# 1.net
KiCad netlist of a schematic drawn in Altium Designer
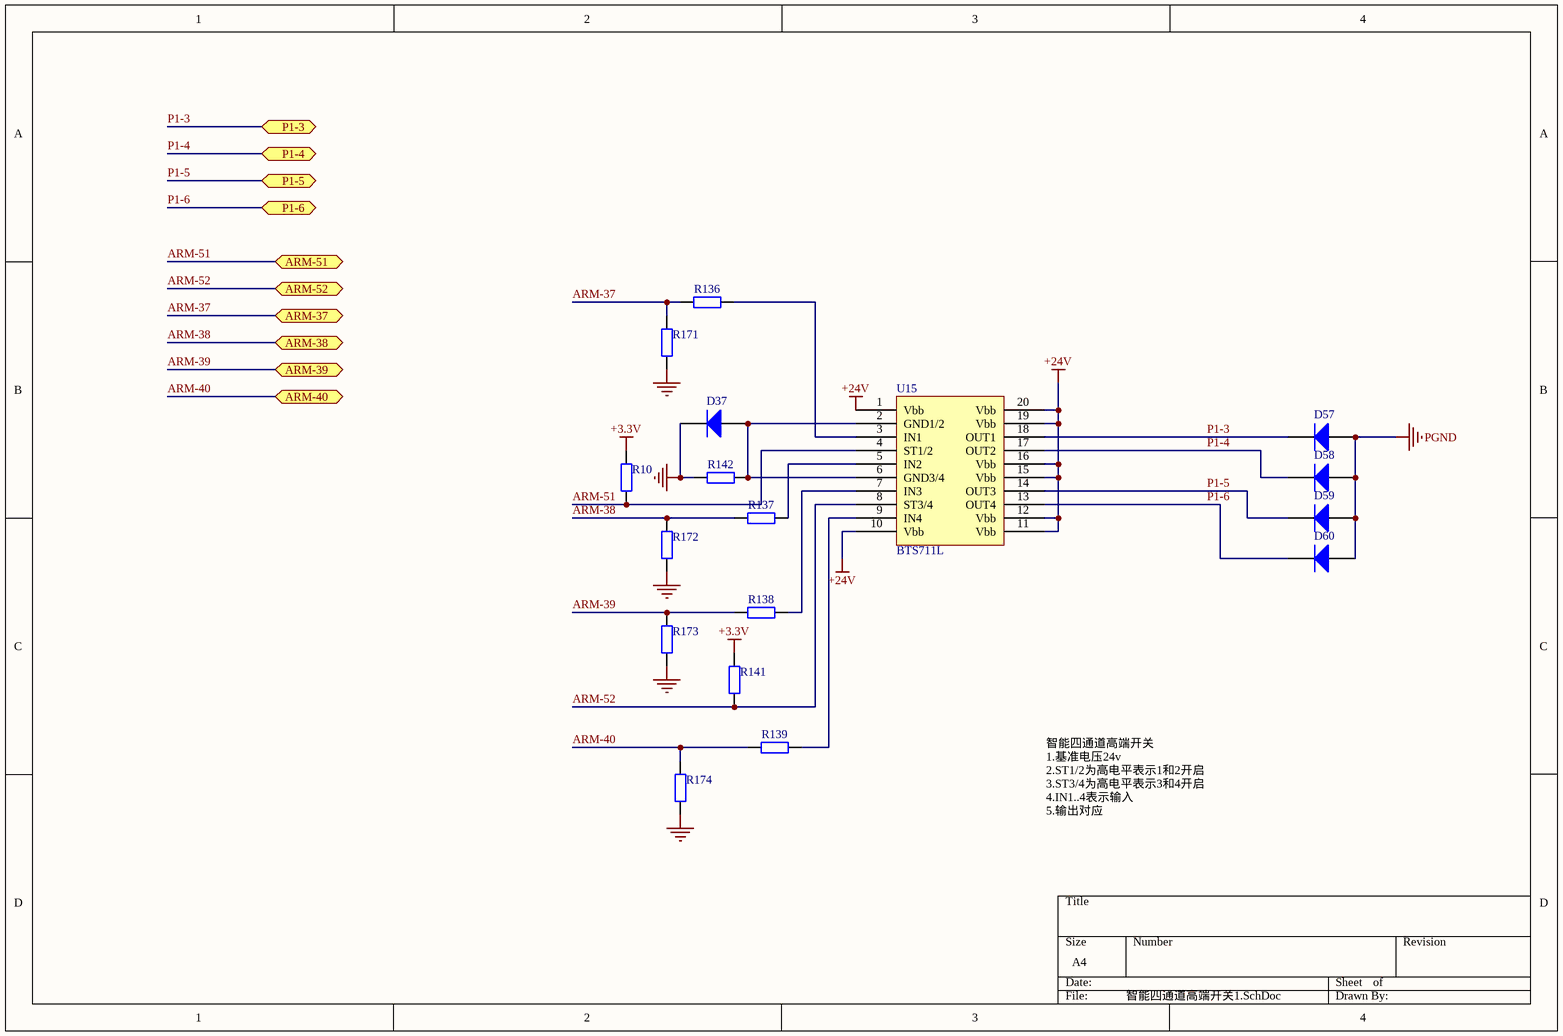
[diagram p0: 智能四通道高端开关1.SchDoc]

(export (version "E")
  (design (tool "Eeschema 10.0.6"))
  (components
    (comp (ref "D37")
      (value "Diode 1N4007")
      (footprint "DO-41")
      (description "1 Amp General Purpose Rectifier")
      (fields (field (name "PUBLISHER") "Altium Limited"))
      (libsource (lib "Miscellaneous Devices") (part "Diode 1N4007"))
    )
    (comp (ref "D57")
      (value "Diode 1N4007")
      (footprint "DO-41")
      (description "1 Amp General Purpose Rectifier")
      (fields (field (name "PUBLISHER") "Altium Limited"))
      (libsource (lib "Miscellaneous Devices") (part "Diode 1N4007"))
    )
    (comp (ref "D58")
      (value "Diode 1N4007")
      (footprint "DO-41")
      (description "1 Amp General Purpose Rectifier")
      (fields (field (name "PUBLISHER") "Altium Limited"))
      (libsource (lib "Miscellaneous Devices") (part "Diode 1N4007"))
    )
    (comp (ref "D59")
      (value "Diode 1N4007")
      (footprint "DO-41")
      (description "1 Amp General Purpose Rectifier")
      (fields (field (name "PUBLISHER") "Altium Limited"))
      (libsource (lib "Miscellaneous Devices") (part "Diode 1N4007"))
    )
    (comp (ref "D60")
      (value "Diode 1N4007")
      (footprint "DO-41")
      (description "1 Amp General Purpose Rectifier")
      (fields (field (name "PUBLISHER") "Altium Limited"))
      (libsource (lib "Miscellaneous Devices") (part "Diode 1N4007"))
    )
    (comp (ref "R10")
      (value "Res2")
      (footprint "AXIAL-0.4")
      (description "Resistor")
      (fields (field (name "PUBLISHER") "Altium Limited"))
      (libsource (lib "Miscellaneous Devices") (part "Res2"))
    )
    (comp (ref "R136")
      (value "Res2")
      (footprint "AXIAL-0.4")
      (description "Resistor")
      (fields (field (name "PUBLISHER") "Altium Limited"))
      (libsource (lib "") (part "Res2_1"))
    )
    (comp (ref "R137")
      (value "Res2")
      (footprint "AXIAL-0.4")
      (description "Resistor")
      (fields (field (name "PUBLISHER") "Altium Limited"))
      (libsource (lib "") (part "Res2_1"))
    )
    (comp (ref "R138")
      (value "Res2")
      (footprint "AXIAL-0.4")
      (description "Resistor")
      (fields (field (name "PUBLISHER") "Altium Limited"))
      (libsource (lib "") (part "Res2_1"))
    )
    (comp (ref "R139")
      (value "Res2")
      (footprint "AXIAL-0.4")
      (description "Resistor")
      (fields (field (name "PUBLISHER") "Altium Limited"))
      (libsource (lib "") (part "Res2_2"))
    )
    (comp (ref "R141")
      (value "Res2")
      (footprint "AXIAL-0.4")
      (description "Resistor")
      (fields (field (name "PUBLISHER") "Altium Limited"))
      (libsource (lib "Miscellaneous Devices") (part "Res2"))
    )
    (comp (ref "R142")
      (value "Res2")
      (footprint "AXIAL-0.4")
      (description "Resistor")
      (fields (field (name "PUBLISHER") "Altium Limited"))
      (libsource (lib "") (part "Res2_1"))
    )
    (comp (ref "R171")
      (value "Res2")
      (footprint "AXIAL-0.4")
      (description "Resistor")
      (fields (field (name "PUBLISHER") "Altium Limited"))
      (libsource (lib "Miscellaneous Devices") (part "Res2"))
    )
    (comp (ref "R172")
      (value "Res2")
      (footprint "AXIAL-0.4")
      (description "Resistor")
      (fields (field (name "PUBLISHER") "Altium Limited"))
      (libsource (lib "Miscellaneous Devices") (part "Res2"))
    )
    (comp (ref "R173")
      (value "Res2")
      (footprint "AXIAL-0.4")
      (description "Resistor")
      (fields (field (name "PUBLISHER") "Altium Limited"))
      (libsource (lib "Miscellaneous Devices") (part "Res2"))
    )
    (comp (ref "R174")
      (value "Res2")
      (footprint "AXIAL-0.4")
      (description "Resistor")
      (fields (field (name "PUBLISHER") "Altium Limited"))
      (libsource (lib "Miscellaneous Devices") (part "Res2"))
    )
    (comp (ref "U15") (value "BTS711L") (libsource (lib "BTS711L1") (part "Component_1")))
  )
  (nets
    (net (code "1") (name "+3.3V") (class "Default")
      (node (ref "R10") (pin "2") (pinfunction "2_2") (pintype "passive"))
      (node (ref "R141") (pin "2") (pinfunction "2_2") (pintype "passive"))
    )
    (net (code "2") (name "+24V") (class "Default")
      (node (ref "U15") (pin "1") (pinfunction "Vbb_1") (pintype "passive"))
      (node (ref "U15") (pin "10") (pinfunction "Vbb_10") (pintype "passive"))
      (node (ref "U15") (pin "11") (pinfunction "Vbb_11") (pintype "passive"))
      (node (ref "U15") (pin "12") (pinfunction "Vbb_12") (pintype "passive"))
      (node (ref "U15") (pin "15") (pinfunction "Vbb_15") (pintype "passive"))
      (node (ref "U15") (pin "16") (pinfunction "Vbb_16") (pintype "passive"))
      (node (ref "U15") (pin "19") (pinfunction "Vbb_19") (pintype "passive"))
      (node (ref "U15") (pin "20") (pinfunction "Vbb_20") (pintype "passive"))
    )
    (net (code "3") (name "/ARM-37") (class "Default")
      (node (ref "R136") (pin "1") (pinfunction "1_1") (pintype "passive"))
      (node (ref "R171") (pin "2") (pinfunction "2_2") (pintype "passive"))
    )
    (net (code "4") (name "/ARM-38") (class "Default")
      (node (ref "R137") (pin "1") (pinfunction "1_1") (pintype "passive"))
      (node (ref "R172") (pin "2") (pinfunction "2_2") (pintype "passive"))
    )
    (net (code "5") (name "/ARM-39") (class "Default")
      (node (ref "R138") (pin "1") (pinfunction "1_1") (pintype "passive"))
      (node (ref "R173") (pin "2") (pinfunction "2_2") (pintype "passive"))
    )
    (net (code "6") (name "/ARM-40") (class "Default")
      (node (ref "R139") (pin "2") (pinfunction "2_2") (pintype "passive"))
      (node (ref "R174") (pin "2") (pinfunction "2_2") (pintype "passive"))
    )
    (net (code "7") (name "/ARM-51") (class "Default")
      (node (ref "R10") (pin "1") (pinfunction "1_1") (pintype "passive"))
      (node (ref "U15") (pin "4") (pinfunction "ST1/2_4") (pintype "passive"))
    )
    (net (code "8") (name "/ARM-52") (class "Default")
      (node (ref "R141") (pin "1") (pinfunction "1_1") (pintype "passive"))
      (node (ref "U15") (pin "8") (pinfunction "ST3/4_8") (pintype "passive"))
    )
    (net (code "9") (name "/P1-3") (class "Default")
      (node (ref "D57") (pin "2") (pinfunction "K_2") (pintype "passive"))
      (node (ref "U15") (pin "18") (pinfunction "OUT1_18") (pintype "passive"))
    )
    (net (code "10") (name "/P1-4") (class "Default")
      (node (ref "D58") (pin "2") (pinfunction "K_2") (pintype "passive"))
      (node (ref "U15") (pin "17") (pinfunction "OUT2_17") (pintype "passive"))
    )
    (net (code "11") (name "/P1-5") (class "Default")
      (node (ref "D59") (pin "2") (pinfunction "K_2") (pintype "passive"))
      (node (ref "U15") (pin "14") (pinfunction "OUT3_14") (pintype "passive"))
    )
    (net (code "12") (name "/P1-6") (class "Default")
      (node (ref "D60") (pin "2") (pinfunction "K_2") (pintype "passive"))
      (node (ref "U15") (pin "13") (pinfunction "OUT4_13") (pintype "passive"))
    )
    (net (code "13") (name "GND") (class "Default")
      (node (ref "D37") (pin "2") (pinfunction "K_2") (pintype "passive"))
      (node (ref "R142") (pin "1") (pinfunction "1_1") (pintype "passive"))
      (node (ref "R171") (pin "1") (pinfunction "1_1") (pintype "passive"))
      (node (ref "R172") (pin "1") (pinfunction "1_1") (pintype "passive"))
      (node (ref "R173") (pin "1") (pinfunction "1_1") (pintype "passive"))
      (node (ref "R174") (pin "1") (pinfunction "1_1") (pintype "passive"))
    )
    (net (code "14") (name "Net-(D37-A)") (class "Default")
      (node (ref "D37") (pin "1") (pinfunction "A_1") (pintype "passive"))
      (node (ref "R142") (pin "2") (pinfunction "2_2") (pintype "passive"))
      (node (ref "U15") (pin "2") (pinfunction "GND1/2_2") (pintype "passive"))
      (node (ref "U15") (pin "6") (pinfunction "GND3/4_6") (pintype "passive"))
    )
    (net (code "15") (name "Net-(U15-IN1)") (class "Default")
      (node (ref "R136") (pin "2") (pinfunction "2_2") (pintype "passive"))
      (node (ref "U15") (pin "3") (pinfunction "IN1_3") (pintype "passive"))
    )
    (net (code "16") (name "Net-(U15-IN2)") (class "Default")
      (node (ref "R137") (pin "2") (pinfunction "2_2") (pintype "passive"))
      (node (ref "U15") (pin "5") (pinfunction "IN2_5") (pintype "passive"))
    )
    (net (code "17") (name "Net-(U15-IN3)") (class "Default")
      (node (ref "R138") (pin "2") (pinfunction "2_2") (pintype "passive"))
      (node (ref "U15") (pin "7") (pinfunction "IN3_7") (pintype "passive"))
    )
    (net (code "18") (name "Net-(U15-IN4)") (class "Default")
      (node (ref "R139") (pin "1") (pinfunction "1_1") (pintype "passive"))
      (node (ref "U15") (pin "9") (pinfunction "IN4_9") (pintype "passive"))
    )
    (net (code "19") (name "PGND") (class "Default")
      (node (ref "D57") (pin "1") (pinfunction "A_1") (pintype "passive"))
      (node (ref "D58") (pin "1") (pinfunction "A_1") (pintype "passive"))
      (node (ref "D59") (pin "1") (pinfunction "A_1") (pintype "passive"))
      (node (ref "D60") (pin "1") (pinfunction "A_1") (pintype "passive"))
    )
  )
)
